# CON_MC_PCI_Express_Mini_J1_52PIN.net
KiCad netlist of a schematic drawn in Altium Designer
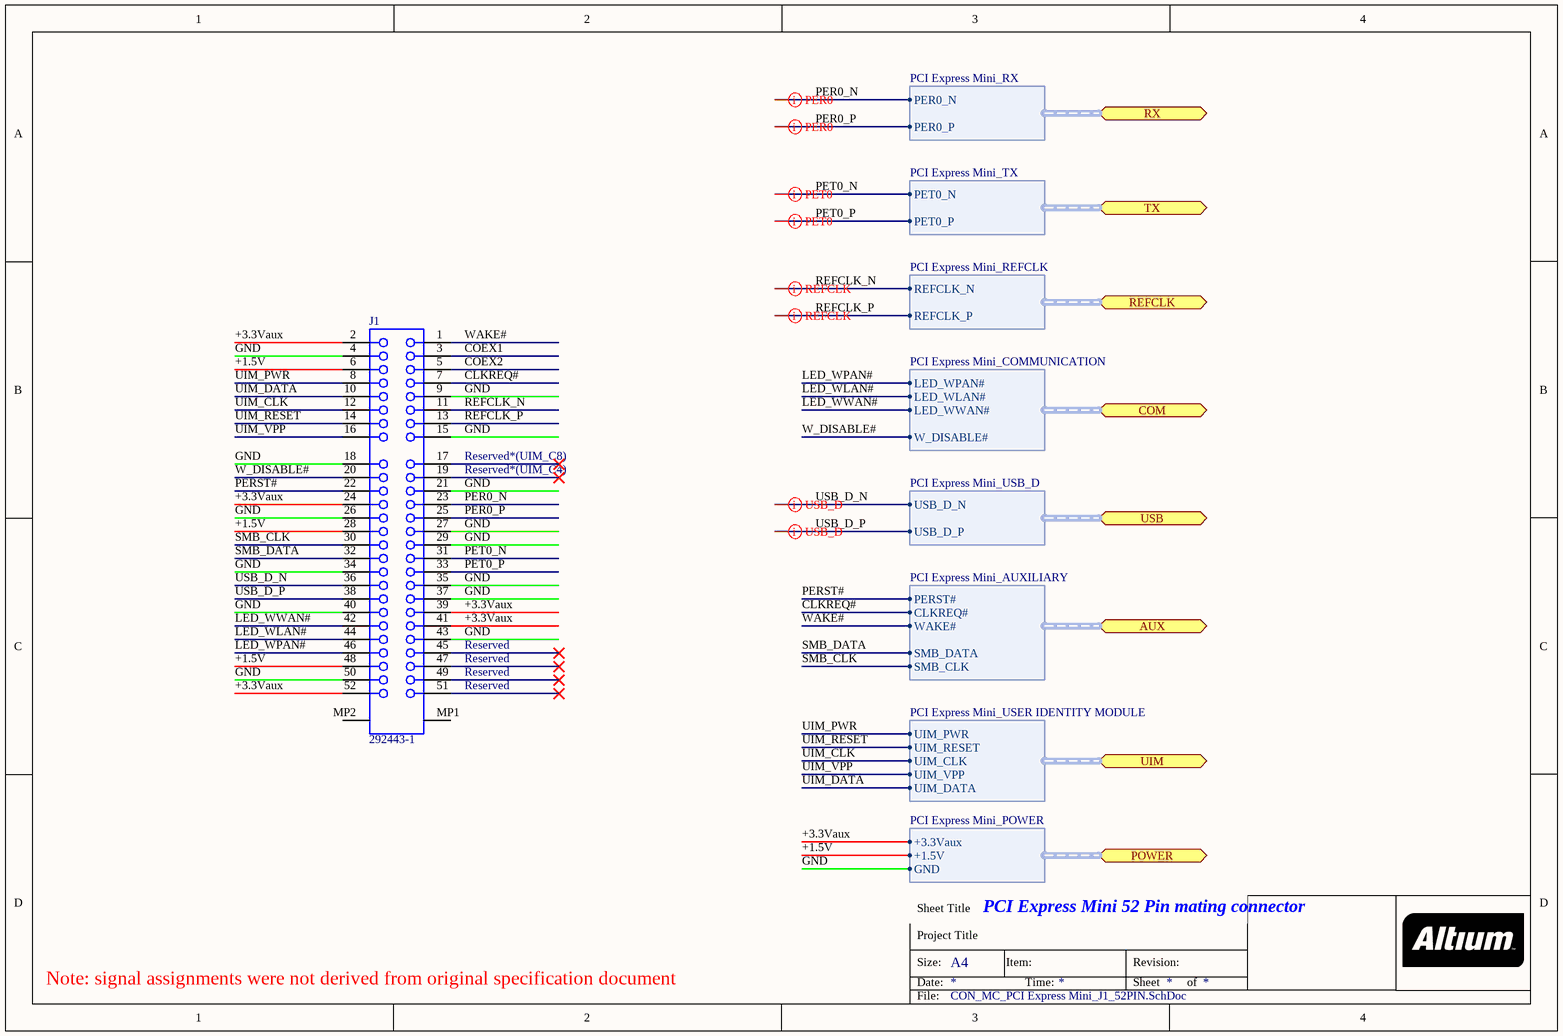
[diagram p0: CON_MC_PCI Express Mini_J1_52PIN.SchDoc]

(export (version "E")
  (design (tool "Eeschema 10.0.6"))
  (components
    (comp (ref "J1")
      (value "292443-1")
      (footprint "BTB-SM0-8-2H52F")
      (description "Board-to-Board Connector, SMT, Right Angle, Pitch 0.8mm, 52-Position, Female")
      (fields (field (name "PUBLISHER") "Altium"))
      (libsource (lib "Altium Shanghai") (part "CMP-0001-00120-1"))
    )
  )
  (nets
    (net (code "13") (name "/+1.5V") (class "Default")
      (node (ref "J1") (pin "28") (pinfunction "28_28") (pintype "passive"))
      (node (ref "J1") (pin "48") (pinfunction "48_48") (pintype "passive"))
      (node (ref "J1") (pin "6") (pinfunction "6_6") (pintype "passive"))
    )
    (net (code "14") (name "/+3.3Vaux") (class "Default")
      (node (ref "J1") (pin "2") (pinfunction "2_2") (pintype "passive"))
      (node (ref "J1") (pin "24") (pinfunction "24_24") (pintype "passive"))
      (node (ref "J1") (pin "39") (pinfunction "39_39") (pintype "passive"))
      (node (ref "J1") (pin "41") (pinfunction "41_41") (pintype "passive"))
      (node (ref "J1") (pin "52") (pinfunction "52_52") (pintype "passive"))
    )
    (net (code "15") (name "/CLKREQ#") (class "Default")
      (node (ref "J1") (pin "7") (pinfunction "7_7") (pintype "passive"))
    )
    (net (code "16") (name "/COEX1") (class "Default")
      (node (ref "J1") (pin "3") (pinfunction "3_3") (pintype "passive"))
    )
    (net (code "17") (name "/COEX2") (class "Default")
      (node (ref "J1") (pin "5") (pinfunction "5_5") (pintype "passive"))
    )
    (net (code "18") (name "/GND") (class "Default")
      (node (ref "J1") (pin "15") (pinfunction "15_15") (pintype "passive"))
      (node (ref "J1") (pin "18") (pinfunction "18_18") (pintype "passive"))
      (node (ref "J1") (pin "21") (pinfunction "21_21") (pintype "passive"))
      (node (ref "J1") (pin "26") (pinfunction "26_26") (pintype "passive"))
      (node (ref "J1") (pin "27") (pinfunction "27_27") (pintype "passive"))
      (node (ref "J1") (pin "29") (pinfunction "29_29") (pintype "passive"))
      (node (ref "J1") (pin "34") (pinfunction "34_34") (pintype "passive"))
      (node (ref "J1") (pin "35") (pinfunction "35_35") (pintype "passive"))
      (node (ref "J1") (pin "37") (pinfunction "37_37") (pintype "passive"))
      (node (ref "J1") (pin "4") (pinfunction "4_4") (pintype "passive"))
      (node (ref "J1") (pin "40") (pinfunction "40_40") (pintype "passive"))
      (node (ref "J1") (pin "43") (pinfunction "43_43") (pintype "passive"))
      (node (ref "J1") (pin "50") (pinfunction "50_50") (pintype "passive"))
      (node (ref "J1") (pin "9") (pinfunction "9_9") (pintype "passive"))
    )
    (net (code "19") (name "/LED_WLAN#") (class "Default")
      (node (ref "J1") (pin "44") (pinfunction "44_44") (pintype "passive"))
    )
    (net (code "20") (name "/LED_WPAN#") (class "Default")
      (node (ref "J1") (pin "46") (pinfunction "46_46") (pintype "passive"))
    )
    (net (code "21") (name "/LED_WWAN#") (class "Default")
      (node (ref "J1") (pin "42") (pinfunction "42_42") (pintype "passive"))
    )
    (net (code "22") (name "/PER0_N") (class "Default")
      (node (ref "J1") (pin "23") (pinfunction "23_23") (pintype "passive"))
    )
    (net (code "23") (name "/PER0_P") (class "Default")
      (node (ref "J1") (pin "25") (pinfunction "25_25") (pintype "passive"))
    )
    (net (code "24") (name "/PERST#") (class "Default")
      (node (ref "J1") (pin "22") (pinfunction "22_22") (pintype "passive"))
    )
    (net (code "25") (name "/PET0_N") (class "Default")
      (node (ref "J1") (pin "31") (pinfunction "31_31") (pintype "passive"))
    )
    (net (code "26") (name "/PET0_P") (class "Default")
      (node (ref "J1") (pin "33") (pinfunction "33_33") (pintype "passive"))
    )
    (net (code "27") (name "/REFCLK_N") (class "Default")
      (node (ref "J1") (pin "11") (pinfunction "11_11") (pintype "passive"))
    )
    (net (code "28") (name "/REFCLK_P") (class "Default")
      (node (ref "J1") (pin "13") (pinfunction "13_13") (pintype "passive"))
    )
    (net (code "29") (name "/SMB_CLK") (class "Default")
      (node (ref "J1") (pin "30") (pinfunction "30_30") (pintype "passive"))
    )
    (net (code "30") (name "/SMB_DATA") (class "Default")
      (node (ref "J1") (pin "32") (pinfunction "32_32") (pintype "passive"))
    )
    (net (code "31") (name "/UIM_CLK") (class "Default")
      (node (ref "J1") (pin "12") (pinfunction "12_12") (pintype "passive"))
    )
    (net (code "32") (name "/UIM_DATA") (class "Default")
      (node (ref "J1") (pin "10") (pinfunction "10_10") (pintype "passive"))
    )
    (net (code "33") (name "/UIM_PWR") (class "Default")
      (node (ref "J1") (pin "8") (pinfunction "8_8") (pintype "passive"))
    )
    (net (code "34") (name "/UIM_RESET") (class "Default")
      (node (ref "J1") (pin "14") (pinfunction "14_14") (pintype "passive"))
    )
    (net (code "35") (name "/UIM_VPP") (class "Default")
      (node (ref "J1") (pin "16") (pinfunction "16_16") (pintype "passive"))
    )
    (net (code "36") (name "/USB_D_N") (class "Default")
      (node (ref "J1") (pin "36") (pinfunction "36_36") (pintype "passive"))
    )
    (net (code "37") (name "/USB_D_P") (class "Default")
      (node (ref "J1") (pin "38") (pinfunction "38_38") (pintype "passive"))
    )
    (net (code "38") (name "/WAKE#") (class "Default")
      (node (ref "J1") (pin "1") (pinfunction "1_1") (pintype "passive"))
    )
    (net (code "39") (name "/W_DISABLE#") (class "Default")
      (node (ref "J1") (pin "20") (pinfunction "20_20") (pintype "passive"))
    )
    (net (code "48") (name "unconnected-(J1-53-PadMP1)") (class "Default")
      (node (ref "J1") (pin "MP1") (pinfunction "53_MP1") (pintype "passive"))
    )
    (net (code "49") (name "unconnected-(J1-54-PadMP2)") (class "Default")
      (node (ref "J1") (pin "MP2") (pinfunction "54_MP2") (pintype "passive"))
    )
    (net (code "50") (name "unconnected-(J1-Pad17)") (class "Default")
      (node (ref "J1") (pin "17") (pinfunction "17_17") (pintype "passive+no_connect"))
    )
    (net (code "51") (name "unconnected-(J1-Pad19)") (class "Default")
      (node (ref "J1") (pin "19") (pinfunction "19_19") (pintype "passive+no_connect"))
    )
    (net (code "52") (name "unconnected-(J1-Pad45)") (class "Default")
      (node (ref "J1") (pin "45") (pinfunction "45_45") (pintype "passive+no_connect"))
    )
    (net (code "53") (name "unconnected-(J1-Pad47)") (class "Default")
      (node (ref "J1") (pin "47") (pinfunction "47_47") (pintype "passive+no_connect"))
    )
    (net (code "54") (name "unconnected-(J1-Pad49)") (class "Default")
      (node (ref "J1") (pin "49") (pinfunction "49_49") (pintype "passive+no_connect"))
    )
    (net (code "55") (name "unconnected-(J1-Pad51)") (class "Default")
      (node (ref "J1") (pin "51") (pinfunction "51_51") (pintype "passive+no_connect"))
    )
  )
)
